# rio.net
KiCad netlist of a schematic drawn in Altium Designer
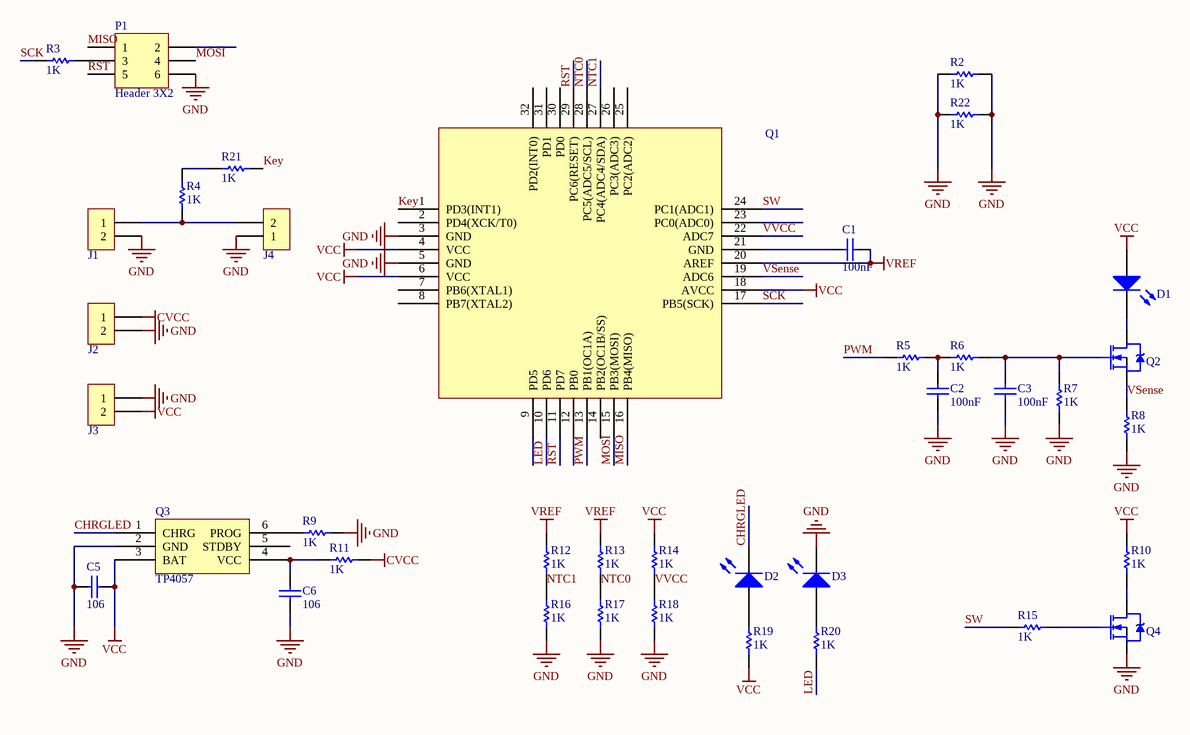
[diagram p0: rio.SchDoc]

(export (version "E")
  (design (tool "Eeschema 10.0.6"))
  (components
    (comp (ref "C1")
      (value "100nF")
      (footprint "0603")
      (description "Capacitor (Semiconductor SIM Model)")
      (fields (field (name "Comment") "Cap Semi") (field (name "PUBLISHER") "Altium Limited"))
      (libsource (lib "scatbasic") (part "Cap Semi"))
    )
    (comp (ref "C2")
      (value "100nF")
      (footprint "0603")
      (description "Capacitor (Semiconductor SIM Model)")
      (fields (field (name "Comment") "Cap Semi") (field (name "PUBLISHER") "Altium Limited"))
      (libsource (lib "scatbasic") (part "Cap Semi"))
    )
    (comp (ref "C3")
      (value "100nF")
      (footprint "0603")
      (description "Capacitor (Semiconductor SIM Model)")
      (fields (field (name "Comment") "Cap Semi") (field (name "PUBLISHER") "Altium Limited"))
      (libsource (lib "scatbasic") (part "Cap Semi"))
    )
    (comp (ref "C5")
      (value "106")
      (footprint "0805")
      (description "Capacitor (Semiconductor SIM Model)")
      (fields (field (name "Comment") "Cap Semi") (field (name "PUBLISHER") "Altium Limited"))
      (libsource (lib "*") (part "Cap Semi"))
    )
    (comp (ref "C6")
      (value "106")
      (footprint "0805")
      (description "Capacitor (Semiconductor SIM Model)")
      (fields (field (name "Comment") "Cap Semi") (field (name "PUBLISHER") "Altium Limited"))
      (libsource (lib "*") (part "Cap Semi"))
    )
    (comp (ref "D1") (value "LED_3W") (footprint "2PIN2.0smd") (libsource (lib "scatbasic") (part "LED_3W")))
    (comp (ref "D2") (value "LED") (footprint "0805") (libsource (lib "scatbasic") (part "LED")))
    (comp (ref "D3") (value "LED") (footprint "0805") (libsource (lib "scatbasic") (part "LED")))
    (comp (ref "J1") (value "2PIN") (footprint "4pin smd key") (libsource (lib "scatbasic") (part "2PIN")))
    (comp (ref "J2") (value "2PIN") (footprint "2PIN2.54 smd") (libsource (lib "scatbasic") (part "2PIN")))
    (comp (ref "J3") (value "2PIN") (footprint "2PIN2.54 smd") (libsource (lib "scatbasic") (part "2PIN")))
    (comp (ref "J4") (value "2PIN") (footprint "smd key 2pin") (libsource (lib "") (part "2PIN_1")))
    (comp (ref "P1")
      (value "Header 3X2")
      (footprint "HDR2X3 - smd")
      (description "Header, 3-Pin, Dual row")
      (fields (field (name "PUBLISHER") "Altium Limited"))
      (libsource (lib "scatbasic") (part "Header 3X2"))
    )
    (comp (ref "Q1") (value "M8") (footprint "TQFP32") (libsource (lib "scatbasic") (part "M8")))
    (comp (ref "Q2")
      (value "NMOS-2")
      (footprint "SOT23")
      (description "N-Channel Power MOSFET")
      (fields (field (name "PUBLISHER") "Altium Limited"))
      (libsource (lib "scatbasic") (part "NMOS-2"))
    )
    (comp (ref "Q3") (value "TP4057") (footprint "SOT26") (libsource (lib "scatbasic") (part "TP4057")))
    (comp (ref "Q4")
      (value "NMOS-2")
      (footprint "SOT23")
      (description "N-Channel Power MOSFET")
      (fields (field (name "PUBLISHER") "Altium Limited"))
      (libsource (lib "scatbasic") (part "NMOS-2"))
    )
    (comp (ref "R2")
      (value "1K")
      (footprint "0805")
      (description "Semiconductor Resistor")
      (fields (field (name "Comment") "Res Semi") (field (name "PUBLISHER") "Altium Limited"))
      (libsource (lib "scatbasic") (part "Res Semi"))
    )
    (comp (ref "R3")
      (value "1K")
      (footprint "0805")
      (description "Semiconductor Resistor")
      (fields (field (name "Comment") "Res Semi") (field (name "PUBLISHER") "Altium Limited"))
      (libsource (lib "scatbasic") (part "Res Semi"))
    )
    (comp (ref "R4")
      (value "1K")
      (footprint "0805")
      (description "Semiconductor Resistor")
      (fields (field (name "Comment") "Res Semi") (field (name "PUBLISHER") "Altium Limited"))
      (libsource (lib "scatbasic") (part "Res Semi"))
    )
    (comp (ref "R5")
      (value "1K")
      (footprint "0603")
      (description "Semiconductor Resistor")
      (fields (field (name "Comment") "Res Semi") (field (name "PUBLISHER") "Altium Limited"))
      (libsource (lib "scatbasic") (part "Res Semi"))
    )
    (comp (ref "R6")
      (value "1K")
      (footprint "0603")
      (description "Semiconductor Resistor")
      (fields (field (name "Comment") "Res Semi") (field (name "PUBLISHER") "Altium Limited"))
      (libsource (lib "scatbasic") (part "Res Semi"))
    )
    (comp (ref "R7")
      (value "1K")
      (footprint "0603")
      (description "Semiconductor Resistor")
      (fields (field (name "Comment") "Res Semi") (field (name "PUBLISHER") "Altium Limited"))
      (libsource (lib "scatbasic") (part "Res Semi"))
    )
    (comp (ref "R8")
      (value "1K")
      (footprint "3216[1206]")
      (description "Semiconductor Resistor")
      (fields (field (name "Comment") "Res Semi") (field (name "PUBLISHER") "Altium Limited"))
      (libsource (lib "scatbasic") (part "Res Semi"))
    )
    (comp (ref "R9")
      (value "1K")
      (footprint "0603")
      (description "Semiconductor Resistor")
      (fields (field (name "Comment") "Res Semi") (field (name "PUBLISHER") "Altium Limited"))
      (libsource (lib "scatbasic") (part "Res Semi"))
    )
    (comp (ref "R10")
      (value "1K")
      (footprint "2PIN2.0smd")
      (description "Semiconductor Resistor")
      (fields (field (name "Comment") "Res Semi") (field (name "PUBLISHER") "Altium Limited"))
      (libsource (lib "scatbasic") (part "Res Semi"))
    )
    (comp (ref "R11")
      (value "1K")
      (footprint "3216[1206]")
      (description "Semiconductor Resistor")
      (fields (field (name "Comment") "Res Semi") (field (name "PUBLISHER") "Altium Limited"))
      (libsource (lib "scatbasic") (part "Res Semi"))
    )
    (comp (ref "R12")
      (value "1K")
      (footprint "0603")
      (description "Semiconductor Resistor")
      (fields (field (name "Comment") "Res Semi") (field (name "PUBLISHER") "Altium Limited"))
      (libsource (lib "scatbasic") (part "Res Semi"))
    )
    (comp (ref "R13")
      (value "1K")
      (footprint "0603")
      (description "Semiconductor Resistor")
      (fields (field (name "Comment") "Res Semi") (field (name "PUBLISHER") "Altium Limited"))
      (libsource (lib "scatbasic") (part "Res Semi"))
    )
    (comp (ref "R14")
      (value "1K")
      (footprint "0603")
      (description "Semiconductor Resistor")
      (fields (field (name "Comment") "Res Semi") (field (name "PUBLISHER") "Altium Limited"))
      (libsource (lib "scatbasic") (part "Res Semi"))
    )
    (comp (ref "R15")
      (value "1K")
      (footprint "0603")
      (description "Semiconductor Resistor")
      (fields (field (name "Comment") "Res Semi") (field (name "PUBLISHER") "Altium Limited"))
      (libsource (lib "scatbasic") (part "Res Semi"))
    )
    (comp (ref "R16")
      (value "1K")
      (footprint "2PIN2.0smd")
      (description "Semiconductor Resistor")
      (fields (field (name "Comment") "Res Semi") (field (name "PUBLISHER") "Altium Limited"))
      (libsource (lib "scatbasic") (part "Res Semi"))
    )
    (comp (ref "R17")
      (value "1K")
      (footprint "2PIN2.0smd")
      (description "Semiconductor Resistor")
      (fields (field (name "Comment") "Res Semi") (field (name "PUBLISHER") "Altium Limited"))
      (libsource (lib "scatbasic") (part "Res Semi"))
    )
    (comp (ref "R18")
      (value "1K")
      (footprint "0603")
      (description "Semiconductor Resistor")
      (fields (field (name "Comment") "Res Semi") (field (name "PUBLISHER") "Altium Limited"))
      (libsource (lib "scatbasic") (part "Res Semi"))
    )
    (comp (ref "R19")
      (value "1K")
      (footprint "0603")
      (description "Semiconductor Resistor")
      (fields (field (name "Comment") "Res Semi") (field (name "PUBLISHER") "Altium Limited"))
      (libsource (lib "scatbasic") (part "Res Semi"))
    )
    (comp (ref "R20")
      (value "1K")
      (footprint "0603")
      (description "Semiconductor Resistor")
      (fields (field (name "Comment") "Res Semi") (field (name "PUBLISHER") "Altium Limited"))
      (libsource (lib "scatbasic") (part "Res Semi"))
    )
    (comp (ref "R21")
      (value "1K")
      (footprint "0805")
      (description "Semiconductor Resistor")
      (fields (field (name "Comment") "Res Semi") (field (name "PUBLISHER") "Altium Limited"))
      (libsource (lib "scatbasic") (part "Res Semi"))
    )
    (comp (ref "R22")
      (value "1K")
      (footprint "0805")
      (description "Semiconductor Resistor")
      (fields (field (name "Comment") "Res Semi") (field (name "PUBLISHER") "Altium Limited"))
      (libsource (lib "scatbasic") (part "Res Semi"))
    )
  )
  (nets
    (net (code "1") (name "/CHRGLED") (class "Default")
      (node (ref "D2") (pin "2") (pinfunction "K_2") (pintype "passive"))
      (node (ref "Q3") (pin "1") (pinfunction "CHRG_1") (pintype "passive"))
    )
    (net (code "2") (name "/Key") (class "Default")
      (node (ref "Q1") (pin "1") (pinfunction "PD3(INT1)_1") (pintype "passive"))
      (node (ref "R21") (pin "1") (pinfunction "1_1") (pintype "passive"))
    )
    (net (code "3") (name "/LED") (class "Default")
      (node (ref "Q1") (pin "10") (pinfunction "PD6_10") (pintype "passive"))
      (node (ref "R20") (pin "1") (pinfunction "1_1") (pintype "passive"))
    )
    (net (code "4") (name "/MISO") (class "Default")
      (node (ref "P1") (pin "1") (pinfunction "1_1") (pintype "passive"))
      (node (ref "Q1") (pin "16") (pinfunction "PB4(MISO)_16") (pintype "passive"))
    )
    (net (code "5") (name "/MOSI") (class "Default")
      (node (ref "P1") (pin "4") (pinfunction "4_4") (pintype "passive"))
      (node (ref "Q1") (pin "15") (pinfunction "PB3(MOSI)_15") (pintype "passive"))
    )
    (net (code "6") (name "/NTC0") (class "Default")
      (node (ref "Q1") (pin "28") (pinfunction "PC5(ADC5/SCL)_28") (pintype "passive"))
      (node (ref "R13") (pin "2") (pinfunction "2_2") (pintype "passive"))
      (node (ref "R17") (pin "2") (pinfunction "2_2") (pintype "passive"))
    )
    (net (code "7") (name "/NTC1") (class "Default")
      (node (ref "Q1") (pin "27") (pinfunction "PC4(ADC4/SDA)_27") (pintype "passive"))
      (node (ref "R12") (pin "2") (pinfunction "2_2") (pintype "passive"))
      (node (ref "R16") (pin "2") (pinfunction "2_2") (pintype "passive"))
    )
    (net (code "8") (name "/PWM") (class "Default")
      (node (ref "Q1") (pin "13") (pinfunction "PB1(OC1A)_13") (pintype "passive"))
      (node (ref "R5") (pin "1") (pinfunction "1_1") (pintype "passive"))
    )
    (net (code "9") (name "/RST") (class "Default")
      (node (ref "P1") (pin "5") (pinfunction "5_5") (pintype "passive"))
      (node (ref "Q1") (pin "11") (pinfunction "PD7_11") (pintype "passive"))
      (node (ref "Q1") (pin "29") (pinfunction "PC6(RESET)_29") (pintype "passive"))
    )
    (net (code "10") (name "/SCK") (class "Default")
      (node (ref "Q1") (pin "17") (pinfunction "PB5(SCK)_17") (pintype "passive"))
      (node (ref "R3") (pin "1") (pinfunction "1_1") (pintype "passive"))
    )
    (net (code "11") (name "/SW") (class "Default")
      (node (ref "Q1") (pin "24") (pinfunction "PC1(ADC1)_24") (pintype "passive"))
      (node (ref "R15") (pin "1") (pinfunction "1_1") (pintype "passive"))
    )
    (net (code "12") (name "/VSense") (class "Default")
      (node (ref "Q1") (pin "19") (pinfunction "ADC6_19") (pintype "passive"))
      (node (ref "Q2") (pin "3") (pinfunction "S_3") (pintype "passive"))
      (node (ref "R8") (pin "1") (pinfunction "1_1") (pintype "passive"))
    )
    (net (code "13") (name "/VVCC") (class "Default")
      (node (ref "Q1") (pin "22") (pinfunction "ADC7_22") (pintype "passive"))
      (node (ref "R14") (pin "2") (pinfunction "2_2") (pintype "passive"))
      (node (ref "R18") (pin "2") (pinfunction "2_2") (pintype "passive"))
    )
    (net (code "14") (name "CVCC") (class "Default")
      (node (ref "J2") (pin "1") (pinfunction "1_1") (pintype "passive"))
      (node (ref "R11") (pin "2") (pinfunction "2_2") (pintype "passive"))
    )
    (net (code "15") (name "GND") (class "Default")
      (node (ref "C2") (pin "1") (pinfunction "1_1") (pintype "passive"))
      (node (ref "C3") (pin "1") (pinfunction "1_1") (pintype "passive"))
      (node (ref "C5") (pin "1") (pinfunction "1_1") (pintype "passive"))
      (node (ref "C6") (pin "1") (pinfunction "1_1") (pintype "passive"))
      (node (ref "D3") (pin "2") (pinfunction "K_2") (pintype "passive"))
      (node (ref "J1") (pin "2") (pinfunction "2_2") (pintype "passive"))
      (node (ref "J2") (pin "2") (pinfunction "2_2") (pintype "passive"))
      (node (ref "J3") (pin "1") (pinfunction "1_1") (pintype "passive"))
      (node (ref "J4") (pin "1") (pinfunction "1_1") (pintype "passive"))
      (node (ref "P1") (pin "6") (pinfunction "6_6") (pintype "passive"))
      (node (ref "Q1") (pin "3") (pinfunction "GND_3") (pintype "passive"))
      (node (ref "Q1") (pin "5") (pinfunction "GND_5") (pintype "passive"))
      (node (ref "Q3") (pin "2") (pinfunction "GND_2") (pintype "passive"))
      (node (ref "Q4") (pin "3") (pinfunction "S_3") (pintype "passive"))
      (node (ref "R16") (pin "1") (pinfunction "1_1") (pintype "passive"))
      (node (ref "R17") (pin "1") (pinfunction "1_1") (pintype "passive"))
      (node (ref "R18") (pin "1") (pinfunction "1_1") (pintype "passive"))
      (node (ref "R2") (pin "1") (pinfunction "1_1") (pintype "passive"))
      (node (ref "R2") (pin "2") (pinfunction "2_2") (pintype "passive"))
      (node (ref "R22") (pin "1") (pinfunction "1_1") (pintype "passive"))
      (node (ref "R22") (pin "2") (pinfunction "2_2") (pintype "passive"))
      (node (ref "R7") (pin "1") (pinfunction "1_1") (pintype "passive"))
      (node (ref "R8") (pin "2") (pinfunction "2_2") (pintype "passive"))
      (node (ref "R9") (pin "1") (pinfunction "1_1") (pintype "passive"))
    )
    (net (code "16") (name "Net-(C1-Pad1)") (class "Default")
      (node (ref "C1") (pin "1") (pinfunction "1_1") (pintype "passive"))
      (node (ref "Q1") (pin "21") (pinfunction "GND_21") (pintype "passive"))
    )
    (net (code "17") (name "Net-(C2-Pad2)") (class "Default")
      (node (ref "C2") (pin "2") (pinfunction "2_2") (pintype "passive"))
      (node (ref "R5") (pin "2") (pinfunction "2_2") (pintype "passive"))
      (node (ref "R6") (pin "1") (pinfunction "1_1") (pintype "passive"))
    )
    (net (code "18") (name "Net-(D1-K)") (class "Default")
      (node (ref "D1") (pin "2") (pinfunction "K_2") (pintype "passive"))
      (node (ref "Q2") (pin "2") (pinfunction "D_2") (pintype "passive"))
    )
    (net (code "19") (name "Net-(D2-A)") (class "Default")
      (node (ref "D2") (pin "1") (pinfunction "A_1") (pintype "passive"))
      (node (ref "R19") (pin "2") (pinfunction "2_2") (pintype "passive"))
    )
    (net (code "20") (name "Net-(D3-A)") (class "Default")
      (node (ref "D3") (pin "1") (pinfunction "A_1") (pintype "passive"))
      (node (ref "R20") (pin "2") (pinfunction "2_2") (pintype "passive"))
    )
    (net (code "21") (name "Net-(J1-Pad1)") (class "Default")
      (node (ref "J1") (pin "1") (pinfunction "1_1") (pintype "passive"))
      (node (ref "J4") (pin "2") (pinfunction "2_2") (pintype "passive"))
      (node (ref "R4") (pin "1") (pinfunction "1_1") (pintype "passive"))
    )
    (net (code "22") (name "Net-(P1-Pad3)") (class "Default")
      (node (ref "P1") (pin "3") (pinfunction "3_3") (pintype "passive"))
      (node (ref "R3") (pin "2") (pinfunction "2_2") (pintype "passive"))
    )
    (net (code "23") (name "Net-(Q2-G)") (class "Default")
      (node (ref "C3") (pin "2") (pinfunction "2_2") (pintype "passive"))
      (node (ref "Q2") (pin "1") (pinfunction "G_1") (pintype "passive"))
      (node (ref "R6") (pin "2") (pinfunction "2_2") (pintype "passive"))
      (node (ref "R7") (pin "2") (pinfunction "2_2") (pintype "passive"))
    )
    (net (code "24") (name "Net-(Q3-PROG)") (class "Default")
      (node (ref "Q3") (pin "6") (pinfunction "PROG_6") (pintype "passive"))
      (node (ref "R9") (pin "2") (pinfunction "2_2") (pintype "passive"))
    )
    (net (code "25") (name "Net-(Q3-VCC)") (class "Default")
      (node (ref "C6") (pin "2") (pinfunction "2_2") (pintype "passive"))
      (node (ref "Q3") (pin "4") (pinfunction "VCC_4") (pintype "passive"))
      (node (ref "R11") (pin "1") (pinfunction "1_1") (pintype "passive"))
    )
    (net (code "26") (name "Net-(Q4-D)") (class "Default")
      (node (ref "Q4") (pin "2") (pinfunction "D_2") (pintype "passive"))
      (node (ref "R10") (pin "2") (pinfunction "2_2") (pintype "passive"))
    )
    (net (code "27") (name "Net-(Q4-G)") (class "Default")
      (node (ref "Q4") (pin "1") (pinfunction "G_1") (pintype "passive"))
      (node (ref "R15") (pin "2") (pinfunction "2_2") (pintype "passive"))
    )
    (net (code "28") (name "Net-(R21-Pad2)") (class "Default")
      (node (ref "R21") (pin "2") (pinfunction "2_2") (pintype "passive"))
      (node (ref "R4") (pin "2") (pinfunction "2_2") (pintype "passive"))
    )
    (net (code "29") (name "VCC") (class "Default")
      (node (ref "C5") (pin "2") (pinfunction "2_2") (pintype "passive"))
      (node (ref "D1") (pin "1") (pinfunction "A_1") (pintype "passive"))
      (node (ref "J3") (pin "2") (pinfunction "2_2") (pintype "passive"))
      (node (ref "Q1") (pin "18") (pinfunction "AVCC_18") (pintype "passive"))
      (node (ref "Q1") (pin "4") (pinfunction "VCC_4") (pintype "passive"))
      (node (ref "Q1") (pin "6") (pinfunction "VCC_6") (pintype "passive"))
      (node (ref "Q3") (pin "3") (pinfunction "BAT_3") (pintype "passive"))
      (node (ref "R10") (pin "1") (pinfunction "1_1") (pintype "passive"))
      (node (ref "R14") (pin "1") (pinfunction "1_1") (pintype "passive"))
      (node (ref "R19") (pin "1") (pinfunction "1_1") (pintype "passive"))
    )
    (net (code "30") (name "VREF") (class "Default")
      (node (ref "C1") (pin "2") (pinfunction "2_2") (pintype "passive"))
      (node (ref "Q1") (pin "20") (pinfunction "AREF_20") (pintype "passive"))
      (node (ref "R12") (pin "1") (pinfunction "1_1") (pintype "passive"))
      (node (ref "R13") (pin "1") (pinfunction "1_1") (pintype "passive"))
    )
    (net (code "31") (name "unconnected-(P1-Pad2)") (class "Default")
      (node (ref "P1") (pin "2") (pinfunction "2_2") (pintype "passive"))
    )
    (net (code "32") (name "unconnected-(Q1-PB0-Pad12)") (class "Default")
      (node (ref "Q1") (pin "12") (pinfunction "PB0_12") (pintype "passive"))
    )
    (net (code "33") (name "unconnected-(Q1-PB2(OC1B{slash}SS)-Pad14)") (class "Default")
      (node (ref "Q1") (pin "14") (pinfunction "PB2(OC1B/SS)_14") (pintype "passive"))
    )
    (net (code "34") (name "unconnected-(Q1-PB6(XTAL1)-Pad7)") (class "Default")
      (node (ref "Q1") (pin "7") (pinfunction "PB6(XTAL1)_7") (pintype "passive"))
    )
    (net (code "35") (name "unconnected-(Q1-PB7(XTAL2)-Pad8)") (class "Default")
      (node (ref "Q1") (pin "8") (pinfunction "PB7(XTAL2)_8") (pintype "passive"))
    )
    (net (code "36") (name "unconnected-(Q1-PC0(ADC0)-Pad23)") (class "Default")
      (node (ref "Q1") (pin "23") (pinfunction "PC0(ADC0)_23") (pintype "passive"))
    )
    (net (code "37") (name "unconnected-(Q1-PC2(ADC2)-Pad25)") (class "Default")
      (node (ref "Q1") (pin "25") (pinfunction "PC2(ADC2)_25") (pintype "passive"))
    )
    (net (code "38") (name "unconnected-(Q1-PC3(ADC3)-Pad26)") (class "Default")
      (node (ref "Q1") (pin "26") (pinfunction "PC3(ADC3)_26") (pintype "passive"))
    )
    (net (code "39") (name "unconnected-(Q1-PD0-Pad30)") (class "Default")
      (node (ref "Q1") (pin "30") (pinfunction "PD0_30") (pintype "passive"))
    )
    (net (code "40") (name "unconnected-(Q1-PD1-Pad31)") (class "Default")
      (node (ref "Q1") (pin "31") (pinfunction "PD1_31") (pintype "passive"))
    )
    (net (code "41") (name "unconnected-(Q1-PD2(INT0)-Pad32)") (class "Default")
      (node (ref "Q1") (pin "32") (pinfunction "PD2(INT0)_32") (pintype "passive"))
    )
    (net (code "42") (name "unconnected-(Q1-PD4(XCK{slash}T0)-Pad2)") (class "Default")
      (node (ref "Q1") (pin "2") (pinfunction "PD4(XCK/T0)_2") (pintype "passive"))
    )
    (net (code "43") (name "unconnected-(Q1-PD5-Pad9)") (class "Default")
      (node (ref "Q1") (pin "9") (pinfunction "PD5_9") (pintype "passive"))
    )
    (net (code "44") (name "unconnected-(Q2-Pad0)") (class "Default")
      (node (ref "Q2") (pin "0") (pinfunction "0_0") (pintype "passive"))
    )
    (net (code "45") (name "unconnected-(Q3-STDBY-Pad5)") (class "Default")
      (node (ref "Q3") (pin "5") (pinfunction "STDBY_5") (pintype "passive"))
    )
    (net (code "46") (name "unconnected-(Q4-Pad0)") (class "Default")
      (node (ref "Q4") (pin "0") (pinfunction "0_0") (pintype "passive"))
    )
  )
)
